# Schematic_Alarm_tone.net
KiCad netlist of a schematic drawn in Altium Designer
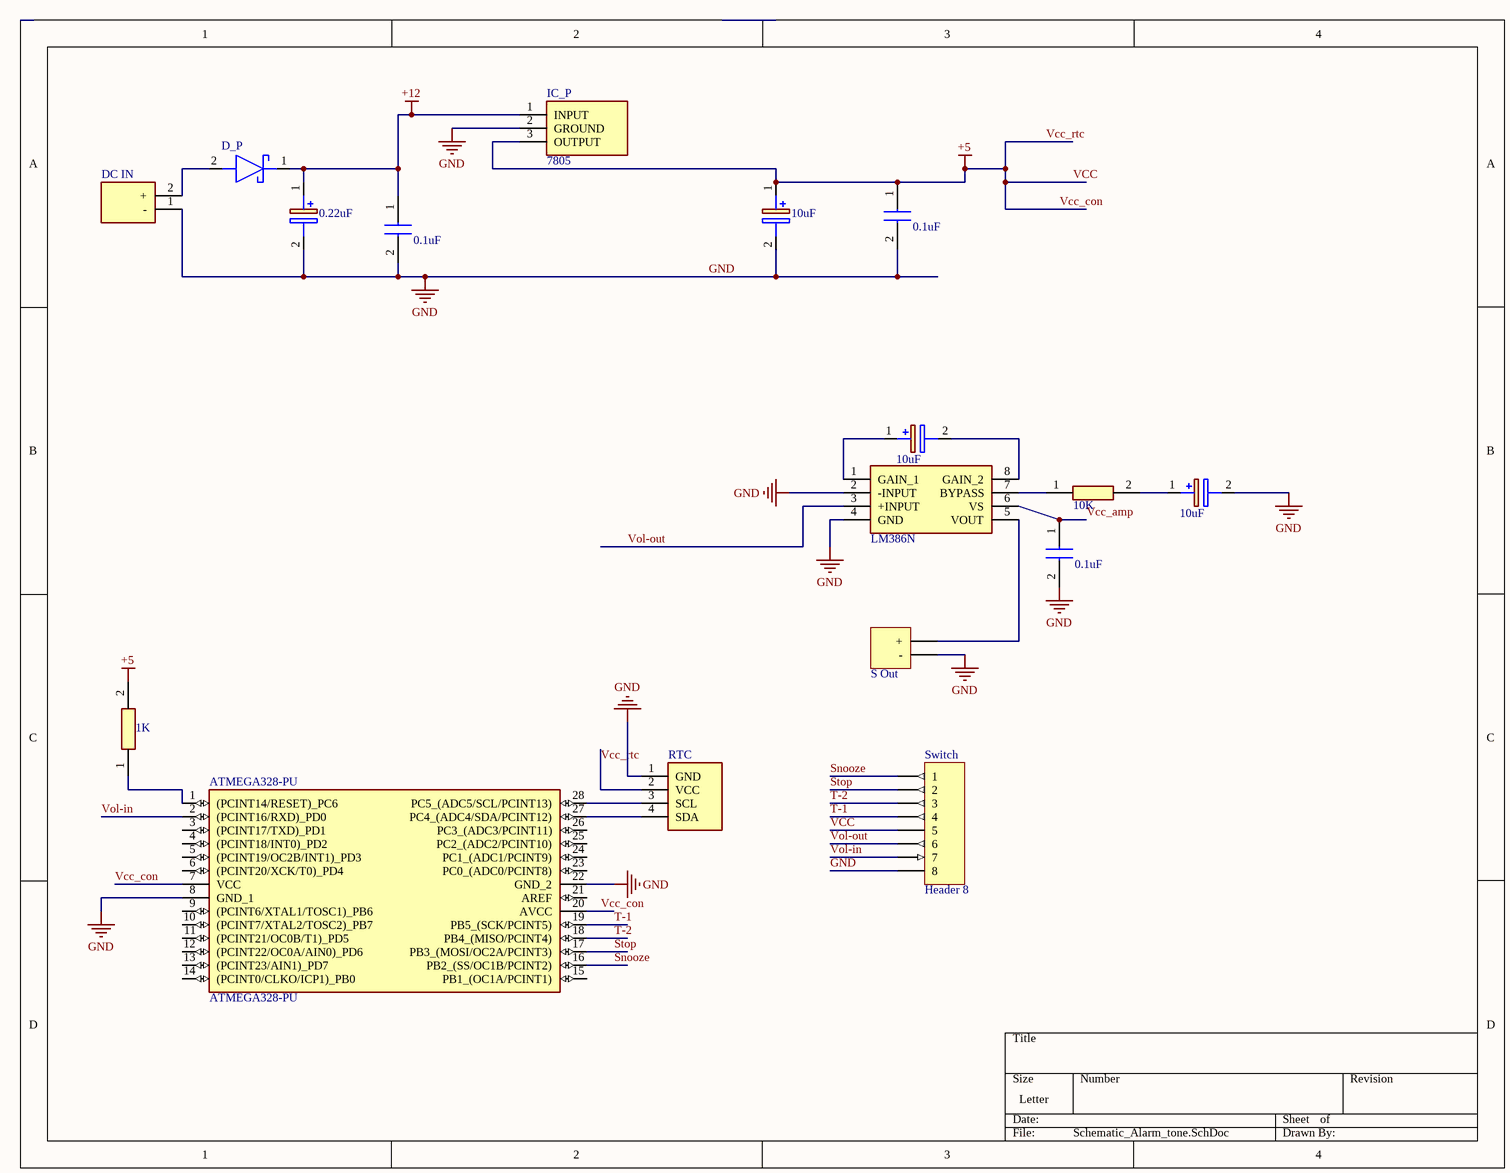
[diagram p0: Schematic_Alarm_tone.SchDoc]

(export (version "E")
  (design (tool "Eeschema 10.0.6"))
  (components
    (comp (ref "ATMEGA328-PU")
      (value "ATMEGA328-PU")
      (footprint "SamacSys:DIP1016W53P254L3468H457Q28N")
      (description "Integrated Circuit")
      (fields (field (name "MOUSER PART NUMBER") "556-ATMEGA328-PU"))
      (libsource (lib "*") (part "ATMEGA328-PU"))
    )
    (comp (ref "C1_A")
      (value "0.1uF")
      (footprint "SamacSys:RCE5C1H103J1A2H03B")
      (description "Capacitor")
      (fields (field (name "MANUFACTURER_PART_NUMBER") "RDER71E104K0K1H03B"))
      (libsource (lib "*") (part "RDER71E104K0K1H03B"))
    )
    (comp (ref "C1_P")
      (value "0.22uF")
      (footprint "SamacSys:CAPPRD200W52D500H1250")
      (description "Capacitor Polarised")
      (fields (field (name "MANUFACTURER_PART_NUMBER") "860010772002"))
      (libsource (lib "*") (part "860010772002"))
    )
    (comp (ref "C2_A")
      (value "10uF")
      (footprint "SamacSys:CAPPRD200W55D500H1250")
      (description "Capacitor Polarised")
      (fields
        (field (name "MOUSER2 PART NUMBER") "667-EEU-FR1H100")
        (field (name "MANUFACTURER_PART_NUMBER") "EEU-FR1H100")
      )
      (libsource (lib "") (part "EEU-FR1H100_1"))
    )
    (comp (ref "C2_P")
      (value "0.1uF")
      (footprint "SamacSys:RCE5C1H103J1A2H03B")
      (description "Capacitor")
      (fields (field (name "MANUFACTURER_PART_NUMBER") "RDER71E104K0K1H03B"))
      (libsource (lib "*") (part "RDER71E104K0K1H03B"))
    )
    (comp (ref "C3_A")
      (value "10uF")
      (footprint "SamacSys:CAPPRD200W55D500H1250")
      (description "Capacitor Polarised")
      (fields
        (field (name "MOUSER2 PART NUMBER") "667-EEU-FR1H100")
        (field (name "MANUFACTURER_PART_NUMBER") "EEU-FR1H100")
      )
      (libsource (lib "") (part "EEU-FR1H100_1"))
    )
    (comp (ref "C3_P")
      (value "10uF")
      (footprint "SamacSys:CAPPRD200W55D500H1250")
      (description "Capacitor Polarised")
      (fields
        (field (name "MOUSER2 PART NUMBER") "667-EEU-FR1H100")
        (field (name "MANUFACTURER_PART_NUMBER") "EEU-FR1H100")
      )
      (libsource (lib "*") (part "EEU-FR1H100"))
    )
    (comp (ref "C4_P")
      (value "0.1uF")
      (footprint "SamacSys:RCE5C1H103J1A2H03B")
      (description "Capacitor")
      (fields (field (name "MANUFACTURER_PART_NUMBER") "RDER71E104K0K1H03B"))
      (libsource (lib "*") (part "RDER71E104K0K1H03B"))
    )
    (comp (ref "DC IN")
      (value "0010845020")
      (footprint "SamacSys:0010845020")
      (description "Connector")
      (libsource (lib "*") (part "0010845020"))
    )
    (comp (ref "D_P")
      (value "SD103A-TR")
      (footprint "SamacSys:DIOAD950W60L350D150")
      (description "Schottky Diode")
      (fields (field (name "MOUSER2 PART NUMBER") "625-SD103A"))
      (libsource (lib "*") (part "SD103A-TR"))
    )
    (comp (ref "H5")
      (value "S Out")
      (footprint "HDR1X2")
      (description "Header, 2-Pin")
      (fields (field (name "PUBLISHER") "Altium Limited"))
      (libsource (lib "Miscellaneous Connectors") (part "Header 2"))
    )
    (comp (ref "IC")
      (value "LM386N")
      (footprint "SamacSys:DIP787W53P254L982H508Q8N")
      (description "Integrated Circuit")
      (fields
        (field (name "MANUFACTURER_PART_NUMBER") "LM386N-4")
        (field (name "MOUSER PART NUMBER") "926-LM386N-4")
      )
      (libsource (lib "*") (part "LM386N-4"))
    )
    (comp (ref "IC_P")
      (value "7805")
      (footprint "SamacSys:TO254P482X997X2018-3P")
      (description "Integrated Circuit")
      (fields
        (field (name "MANUFACTURER_PART_NUMBER") "MC7805CTG")
        (field (name "MOUSER PART NUMBER") "863-MC7805CTG")
      )
      (libsource (lib "*") (part "MC7805CTG"))
    )
    (comp (ref "R1_amp")
      (value "10K")
      (footprint "SamacSys:RESAD1650W60L650D250")
      (description "Resistor")
      (fields
        (field (name "MANUFACTURER_PART_NUMBER") "MRS25000C1002FRP00")
        (field (name "MOUSER PART NUMBER") "594-MRS2510K00F")
      )
      (libsource (lib "*") (part "MRS25000C1002FRP00"))
    )
    (comp (ref "R1_reset")
      (value "1K")
      (footprint "SamacSys:RESAD1680W59L680D250")
      (description "Resistor")
      (fields (field (name "MANUFACTURER_PART_NUMBER") "MF25 1K2"))
      (libsource (lib "*") (part "MF25_1K2"))
    )
    (comp (ref "RTC")
      (value "0022032041")
      (footprint "SamacSys:HDRV4W87P0X254_1X4_991X236X1155P")
      (description "Connector")
      (libsource (lib "*") (part "0022032041"))
    )
    (comp (ref "Switch")
      (value "Header 8")
      (footprint "HDR1X8")
      (description "Header, 8-Pin")
      (fields (field (name "PUBLISHER") "Altium Limited"))
      (libsource (lib "Miscellaneous Connectors") (part "Header 8"))
    )
  )
  (nets
    (net (code "1") (name "+5") (class "Default")
      (node (ref "ATMEGA328-PU") (pin "20") (pinfunction "AVCC_20") (pintype "power_in"))
      (node (ref "ATMEGA328-PU") (pin "7") (pinfunction "VCC_7") (pintype "power_in"))
      (node (ref "C3_P") (pin "1") (pinfunction "+_1") (pintype "power_in"))
      (node (ref "C4_P") (pin "1") (pinfunction "1_1") (pintype "passive"))
      (node (ref "IC_P") (pin "3") (pinfunction "OUTPUT_3") (pintype "power_in"))
      (node (ref "R1_reset") (pin "2") (pinfunction "2_2") (pintype "passive"))
      (node (ref "RTC") (pin "2") (pinfunction "VCC_2") (pintype "passive"))
      (node (ref "Switch") (pin "5") (pinfunction "5_5") (pintype "power_in"))
    )
    (net (code "2") (name "+12") (class "Default")
      (node (ref "C1_P") (pin "1") (pinfunction "+_1") (pintype "passive"))
      (node (ref "C2_P") (pin "1") (pinfunction "1_1") (pintype "passive"))
      (node (ref "D_P") (pin "1") (pinfunction "K_1") (pintype "passive"))
      (node (ref "IC_P") (pin "1") (pinfunction "INPUT_1") (pintype "power_in"))
    )
    (net (code "4") (name "/Snooze") (class "Default")
      (node (ref "ATMEGA328-PU") (pin "16") (pinfunction "PB2_(SS/OC1B/PCINT2)_16") (pintype "bidirectional"))
      (node (ref "Switch") (pin "1") (pinfunction "1_1") (pintype "output"))
    )
    (net (code "5") (name "/Stop") (class "Default")
      (node (ref "ATMEGA328-PU") (pin "17") (pinfunction "PB3_(MOSI/OC2A/PCINT3)_17") (pintype "bidirectional"))
      (node (ref "Switch") (pin "2") (pinfunction "2_2") (pintype "output"))
    )
    (net (code "6") (name "/T-1") (class "Default")
      (node (ref "ATMEGA328-PU") (pin "19") (pinfunction "PB5_(SCK/PCINT5)_19") (pintype "bidirectional"))
      (node (ref "Switch") (pin "4") (pinfunction "4_4") (pintype "output"))
    )
    (net (code "7") (name "/T-2") (class "Default")
      (node (ref "ATMEGA328-PU") (pin "18") (pinfunction "PB4_(MISO/PCINT4)_18") (pintype "bidirectional"))
      (node (ref "Switch") (pin "3") (pinfunction "3_3") (pintype "output"))
    )
    (net (code "8") (name "/Vcc_amp") (class "Default")
      (node (ref "C1_A") (pin "1") (pinfunction "1_1") (pintype "passive"))
      (node (ref "IC") (pin "6") (pinfunction "VS_6") (pintype "passive"))
    )
    (net (code "9") (name "/Vol-in") (class "Default")
      (node (ref "ATMEGA328-PU") (pin "2") (pinfunction "(PCINT16/RXD)_PD0_2") (pintype "bidirectional"))
      (node (ref "Switch") (pin "7") (pinfunction "7_7") (pintype "input"))
    )
    (net (code "10") (name "/Vol-out") (class "Default")
      (node (ref "IC") (pin "3") (pinfunction "+INPUT_3") (pintype "passive"))
      (node (ref "Switch") (pin "6") (pinfunction "6_6") (pintype "output"))
    )
    (net (code "11") (name "GND") (class "Default")
      (node (ref "ATMEGA328-PU") (pin "22") (pinfunction "GND_2_22") (pintype "power_in"))
      (node (ref "ATMEGA328-PU") (pin "8") (pinfunction "GND_1_8") (pintype "power_in"))
      (node (ref "C1_A") (pin "2") (pinfunction "2_2") (pintype "passive"))
      (node (ref "C1_P") (pin "2") (pinfunction "-_2") (pintype "passive"))
      (node (ref "C2_P") (pin "2") (pinfunction "2_2") (pintype "passive"))
      (node (ref "C3_A") (pin "2") (pinfunction "-_2") (pintype "power_in"))
      (node (ref "C3_P") (pin "2") (pinfunction "-_2") (pintype "power_in"))
      (node (ref "C4_P") (pin "2") (pinfunction "2_2") (pintype "passive"))
      (node (ref "DC IN") (pin "1") (pinfunction "-_1") (pintype "power_in"))
      (node (ref "H5") (pin "1") (pinfunction "-_1") (pintype "passive"))
      (node (ref "IC") (pin "2") (pinfunction "-INPUT_2") (pintype "passive"))
      (node (ref "IC") (pin "4") (pinfunction "GND_4") (pintype "passive"))
      (node (ref "IC_P") (pin "2") (pinfunction "GROUND_2") (pintype "power_in"))
      (node (ref "RTC") (pin "1") (pinfunction "GND_1") (pintype "passive"))
      (node (ref "Switch") (pin "8") (pinfunction "8_8") (pintype "power_in"))
    )
    (net (code "12") (name "Net-(ATMEGA328-PU-(PCINT14{slash}RESET)_PC6)") (class "Default")
      (node (ref "ATMEGA328-PU") (pin "1") (pinfunction "(PCINT14/RESET)_PC6_1") (pintype "bidirectional"))
      (node (ref "R1_reset") (pin "1") (pinfunction "1_1") (pintype "passive"))
    )
    (net (code "13") (name "Net-(ATMEGA328-PU-PC4_(ADC4{slash}SDA{slash}PCINT12))") (class "Default")
      (node (ref "ATMEGA328-PU") (pin "27") (pinfunction "PC4_(ADC4/SDA/PCINT12)_27") (pintype "bidirectional"))
      (node (ref "RTC") (pin "4") (pinfunction "SDA_4") (pintype "passive"))
    )
    (net (code "14") (name "Net-(ATMEGA328-PU-PC5_(ADC5{slash}SCL{slash}PCINT13))") (class "Default")
      (node (ref "ATMEGA328-PU") (pin "28") (pinfunction "PC5_(ADC5/SCL/PCINT13)_28") (pintype "bidirectional"))
      (node (ref "RTC") (pin "3") (pinfunction "SCL_3") (pintype "passive"))
    )
    (net (code "15") (name "Net-(C2_A-+)") (class "Default")
      (node (ref "C2_A") (pin "1") (pinfunction "+_1") (pintype "power_in"))
      (node (ref "IC") (pin "1") (pinfunction "GAIN_1_1") (pintype "passive"))
    )
    (net (code "16") (name "Net-(C2_A--)") (class "Default")
      (node (ref "C2_A") (pin "2") (pinfunction "-_2") (pintype "power_in"))
      (node (ref "IC") (pin "8") (pinfunction "GAIN_2_8") (pintype "passive"))
    )
    (net (code "17") (name "Net-(C3_A-+)") (class "Default")
      (node (ref "C3_A") (pin "1") (pinfunction "+_1") (pintype "power_in"))
      (node (ref "R1_amp") (pin "2") (pinfunction "2_2") (pintype "passive"))
    )
    (net (code "18") (name "Net-(DC IN-+)") (class "Default")
      (node (ref "DC IN") (pin "2") (pinfunction "+_2") (pintype "power_in"))
      (node (ref "D_P") (pin "2") (pinfunction "A_2") (pintype "passive"))
    )
    (net (code "19") (name "Net-(H5-+)") (class "Default")
      (node (ref "H5") (pin "2") (pinfunction "+_2") (pintype "passive"))
      (node (ref "IC") (pin "5") (pinfunction "VOUT_5") (pintype "passive"))
    )
    (net (code "20") (name "Net-(IC-BYPASS)") (class "Default")
      (node (ref "IC") (pin "7") (pinfunction "BYPASS_7") (pintype "passive"))
      (node (ref "R1_amp") (pin "1") (pinfunction "1_1") (pintype "passive"))
    )
    (net (code "21") (name "unconnected-(ATMEGA328-PU-(PCINT0{slash}CLKO{slash}ICP1)_PB0-Pad14)") (class "Default")
      (node (ref "ATMEGA328-PU") (pin "14") (pinfunction "(PCINT0/CLKO/ICP1)_PB0_14") (pintype "bidirectional"))
    )
    (net (code "22") (name "unconnected-(ATMEGA328-PU-(PCINT6{slash}XTAL1{slash}TOSC1)_PB6-Pad9)") (class "Default")
      (node (ref "ATMEGA328-PU") (pin "9") (pinfunction "(PCINT6/XTAL1/TOSC1)_PB6_9") (pintype "bidirectional"))
    )
    (net (code "23") (name "unconnected-(ATMEGA328-PU-(PCINT7{slash}XTAL2{slash}TOSC2)_PB7-Pad10)") (class "Default")
      (node (ref "ATMEGA328-PU") (pin "10") (pinfunction "(PCINT7/XTAL2/TOSC2)_PB7_10") (pintype "bidirectional"))
    )
    (net (code "24") (name "unconnected-(ATMEGA328-PU-(PCINT17{slash}TXD)_PD1-Pad3)") (class "Default")
      (node (ref "ATMEGA328-PU") (pin "3") (pinfunction "(PCINT17/TXD)_PD1_3") (pintype "bidirectional"))
    )
    (net (code "25") (name "unconnected-(ATMEGA328-PU-(PCINT18{slash}INT0)_PD2-Pad4)") (class "Default")
      (node (ref "ATMEGA328-PU") (pin "4") (pinfunction "(PCINT18/INT0)_PD2_4") (pintype "bidirectional"))
    )
    (net (code "26") (name "unconnected-(ATMEGA328-PU-(PCINT19{slash}OC2B{slash}INT1)_PD3-Pad5)") (class "Default")
      (node (ref "ATMEGA328-PU") (pin "5") (pinfunction "(PCINT19/OC2B/INT1)_PD3_5") (pintype "bidirectional"))
    )
    (net (code "27") (name "unconnected-(ATMEGA328-PU-(PCINT20{slash}XCK{slash}T0)_PD4-Pad6)") (class "Default")
      (node (ref "ATMEGA328-PU") (pin "6") (pinfunction "(PCINT20/XCK/T0)_PD4_6") (pintype "bidirectional"))
    )
    (net (code "28") (name "unconnected-(ATMEGA328-PU-(PCINT21{slash}OC0B{slash}T1)_PD5-Pad11)") (class "Default")
      (node (ref "ATMEGA328-PU") (pin "11") (pinfunction "(PCINT21/OC0B/T1)_PD5_11") (pintype "bidirectional"))
    )
    (net (code "29") (name "unconnected-(ATMEGA328-PU-(PCINT22{slash}OC0A{slash}AIN0)_PD6-Pad12)") (class "Default")
      (node (ref "ATMEGA328-PU") (pin "12") (pinfunction "(PCINT22/OC0A/AIN0)_PD6_12") (pintype "bidirectional"))
    )
    (net (code "30") (name "unconnected-(ATMEGA328-PU-(PCINT23{slash}AIN1)_PD7-Pad13)") (class "Default")
      (node (ref "ATMEGA328-PU") (pin "13") (pinfunction "(PCINT23/AIN1)_PD7_13") (pintype "bidirectional"))
    )
    (net (code "31") (name "unconnected-(ATMEGA328-PU-AREF-Pad21)") (class "Default")
      (node (ref "ATMEGA328-PU") (pin "21") (pinfunction "AREF_21") (pintype "bidirectional"))
    )
    (net (code "32") (name "unconnected-(ATMEGA328-PU-PB1_(OC1A{slash}PCINT1)-Pad15)") (class "Default")
      (node (ref "ATMEGA328-PU") (pin "15") (pinfunction "PB1_(OC1A/PCINT1)_15") (pintype "bidirectional"))
    )
    (net (code "33") (name "unconnected-(ATMEGA328-PU-PC0_(ADC0{slash}PCINT8)-Pad23)") (class "Default")
      (node (ref "ATMEGA328-PU") (pin "23") (pinfunction "PC0_(ADC0/PCINT8)_23") (pintype "bidirectional"))
    )
    (net (code "34") (name "unconnected-(ATMEGA328-PU-PC1_(ADC1{slash}PCINT9)-Pad24)") (class "Default")
      (node (ref "ATMEGA328-PU") (pin "24") (pinfunction "PC1_(ADC1/PCINT9)_24") (pintype "bidirectional"))
    )
    (net (code "35") (name "unconnected-(ATMEGA328-PU-PC2_(ADC2{slash}PCINT10)-Pad25)") (class "Default")
      (node (ref "ATMEGA328-PU") (pin "25") (pinfunction "PC2_(ADC2/PCINT10)_25") (pintype "bidirectional"))
    )
    (net (code "36") (name "unconnected-(ATMEGA328-PU-PC3_(ADC3{slash}PCINT11)-Pad26)") (class "Default")
      (node (ref "ATMEGA328-PU") (pin "26") (pinfunction "PC3_(ADC3/PCINT11)_26") (pintype "bidirectional"))
    )
  )
)
